# MCU.net
KiCad netlist of a schematic drawn in Altium Designer
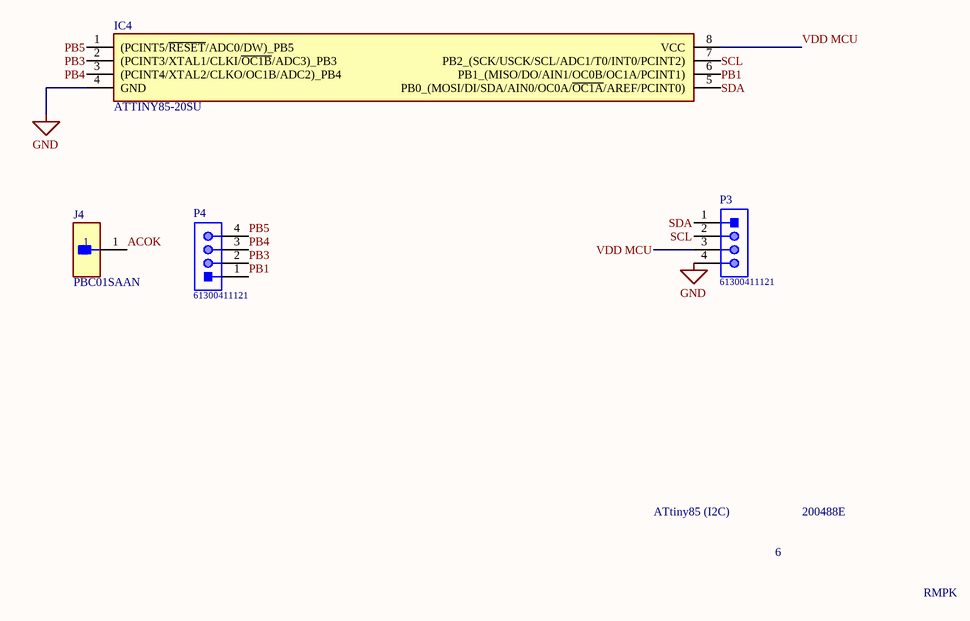
[diagram p0: MCU.SchDoc]

(export (version "E")
  (design (tool "Eeschema 10.0.6"))
  (components
    (comp (ref "IC4")
      (value "ATTINY85-20SU")
      (footprint "SamacSys:SOIC127P798X216-8N")
      (description "Integrated Circuit")
      (fields (field (name "MOUSER PART NUMBER") "556-ATTINY85-20SU"))
      (libsource (lib "SamacSys") (part "ATTINY85-20SU"))
    )
    (comp (ref "J4")
      (value "PBC01SAAN")
      (footprint "FP-PBC01SAAN-MFG")
      (description "CONN HEADER VERT 1POS")
      (libsource (lib "Altium Content Vault") (part "dd45045ce8184df9e99e12baf3f412c"))
    )
    (comp (ref "P3")
      (value "61300411121")
      (footprint "61300411121")
      (description "THT Vertical Pin Header WR-PHD, Pitch 2.54 mm, Single Row, 4 pins")
      (fields (field (name "MANUFACTURER") "Wurth Elektronik") (field (name "PUBLISHER") "WurthElektronik"))
      (libsource (lib "Altium Content Vault") (part "WE-CN-1P-M-R4"))
    )
    (comp (ref "P4")
      (value "61300411121")
      (footprint "61300411121")
      (description "THT Vertical Pin Header WR-PHD, Pitch 2.54 mm, Single Row, 4 pins")
      (fields (field (name "MANUFACTURER") "Wurth Elektronik") (field (name "PUBLISHER") "WurthElektronik"))
      (libsource (lib "") (part "WE-CN-1P-M-R4_1"))
    )
  )
  (nets
    (net (code "1") (name "/ACOK") (class "Default")
      (node (ref "J4") (pin "1") (pinfunction "1_1") (pintype "passive"))
    )
    (net (code "2") (name "/PB1") (class "Default")
      (node (ref "IC4") (pin "6") (pinfunction "PB1_(MISO/DO/AIN1/OC0B/OC1A/PCINT1)_6") (pintype "passive"))
      (node (ref "P4") (pin "1") (pinfunction "1_1") (pintype "passive"))
    )
    (net (code "3") (name "/PB3") (class "Default")
      (node (ref "IC4") (pin "2") (pinfunction "(PCINT3/XTAL1/CLKI/~{OC1B}/ADC3)_PB3_2") (pintype "passive"))
      (node (ref "P4") (pin "2") (pinfunction "2_2") (pintype "passive"))
    )
    (net (code "4") (name "/PB4") (class "Default")
      (node (ref "IC4") (pin "3") (pinfunction "(PCINT4/XTAL2/CLKO/OC1B/ADC2)_PB4_3") (pintype "passive"))
      (node (ref "P4") (pin "3") (pinfunction "3_3") (pintype "passive"))
    )
    (net (code "5") (name "/PB5") (class "Default")
      (node (ref "IC4") (pin "1") (pinfunction "(PCINT5/~{RESET}/ADC0/DW)_PB5_1") (pintype "passive"))
      (node (ref "P4") (pin "4") (pinfunction "4_4") (pintype "passive"))
    )
    (net (code "6") (name "/SCL") (class "Default")
      (node (ref "IC4") (pin "7") (pinfunction "PB2_(SCK/USCK/SCL/ADC1/T0/INT0/PCINT2)_7") (pintype "passive"))
      (node (ref "P3") (pin "2") (pinfunction "2_2") (pintype "passive"))
    )
    (net (code "7") (name "/SDA") (class "Default")
      (node (ref "IC4") (pin "5") (pinfunction "PB0_(MOSI/DI/SDA/AIN0/OC0A/~{OC1A}/AREF/PCINT0)_5") (pintype "passive"))
      (node (ref "P3") (pin "1") (pinfunction "1_1") (pintype "passive"))
    )
    (net (code "8") (name "/VDD MCU") (class "Default")
      (node (ref "IC4") (pin "8") (pinfunction "VCC_8") (pintype "passive"))
      (node (ref "P3") (pin "3") (pinfunction "3_3") (pintype "passive"))
    )
    (net (code "9") (name "GND") (class "Default")
      (node (ref "IC4") (pin "4") (pinfunction "GND_4") (pintype "passive"))
      (node (ref "P3") (pin "4") (pinfunction "4_4") (pintype "passive"))
    )
  )
)
